# hall-lamp.net
KiCad netlist of a schematic drawn in EAGLE
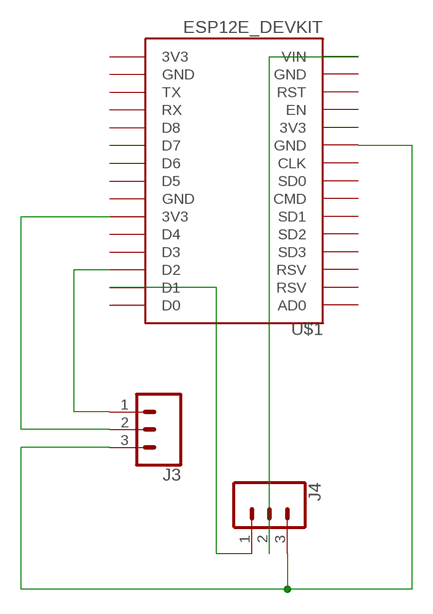
[diagram p0: schematic, sheet 1]

(export (version "E")
  (design (tool "Eeschema 10.0.6"))
  (components
    (comp (ref "J3")
      (value "CONN_03")
      (footprint "eagle-import:1X03")
      (libsource (lib "eagle-import") (part "CONN_03"))
    )
    (comp (ref "J4")
      (value "CONN_03")
      (footprint "eagle-import:1X03")
      (libsource (lib "eagle-import") (part "CONN_03"))
    )
    (comp (ref "U$1")
      (value "ESP12E_DEVKIT")
      (footprint "eagle-import:ESP12E_DEVKIT")
      (libsource (lib "eagle-import") (part "ESP12E_DEVKIT"))
    )
  )
  (nets
    (net (code "1") (name "Net-(J3-Pad1)") (class "Default")
      (node (ref "J3") (pin "1") (pinfunction "1_1") (pintype "passive"))
      (node (ref "U$1") (pin "D2") (pinfunction "D2_D2") (pintype "bidirectional"))
    )
    (net (code "2") (name "Net-(J3-Pad2)") (class "Default")
      (node (ref "J3") (pin "2") (pinfunction "2_2") (pintype "passive"))
      (node (ref "U$1") (pin "3V3@1") (pinfunction "3V3_3V3@1") (pintype "bidirectional"))
    )
    (net (code "3") (name "Net-(J3-Pad3)") (class "Default")
      (node (ref "J3") (pin "3") (pinfunction "3_3") (pintype "passive"))
      (node (ref "J4") (pin "3") (pinfunction "3_3") (pintype "passive"))
      (node (ref "U$1") (pin "GND@0") (pinfunction "GND_GND@0") (pintype "bidirectional"))
    )
    (net (code "4") (name "Net-(J4-Pad1)") (class "Default")
      (node (ref "J4") (pin "1") (pinfunction "1_1") (pintype "passive"))
      (node (ref "U$1") (pin "D1") (pinfunction "D1_D1") (pintype "bidirectional"))
    )
    (net (code "5") (name "Net-(J4-Pad2)") (class "Default")
      (node (ref "J4") (pin "2") (pinfunction "2_2") (pintype "passive"))
      (node (ref "U$1") (pin "VIN") (pinfunction "VIN_VIN") (pintype "bidirectional"))
    )
    (net (code "6") (name "unconnected-(U$1-3V3-Pad3V3@0)") (class "Default")
      (node (ref "U$1") (pin "3V3@0") (pinfunction "3V3_3V3@0") (pintype "bidirectional"))
    )
    (net (code "7") (name "unconnected-(U$1-3V3-Pad3V3@2)") (class "Default")
      (node (ref "U$1") (pin "3V3@2") (pinfunction "3V3_3V3@2") (pintype "bidirectional"))
    )
    (net (code "8") (name "unconnected-(U$1-GND-PadGND@1)") (class "Default")
      (node (ref "U$1") (pin "GND@1") (pinfunction "GND_GND@1") (pintype "bidirectional"))
    )
    (net (code "9") (name "unconnected-(U$1-GND-PadGND@2)") (class "Default")
      (node (ref "U$1") (pin "GND@2") (pinfunction "GND_GND@2") (pintype "bidirectional"))
    )
    (net (code "10") (name "unconnected-(U$1-GND-PadGND@3)") (class "Default")
      (node (ref "U$1") (pin "GND@3") (pinfunction "GND_GND@3") (pintype "bidirectional"))
    )
    (net (code "11") (name "unconnected-(U$1-PadAD0)") (class "Default")
      (node (ref "U$1") (pin "AD0") (pinfunction "AD0_AD0") (pintype "bidirectional"))
    )
    (net (code "12") (name "unconnected-(U$1-PadCLK)") (class "Default")
      (node (ref "U$1") (pin "CLK") (pinfunction "CLK_CLK") (pintype "bidirectional"))
    )
    (net (code "13") (name "unconnected-(U$1-PadCMD)") (class "Default")
      (node (ref "U$1") (pin "CMD") (pinfunction "CMD_CMD") (pintype "bidirectional"))
    )
    (net (code "14") (name "unconnected-(U$1-PadD0)") (class "Default")
      (node (ref "U$1") (pin "D0") (pinfunction "D0_D0") (pintype "bidirectional"))
    )
    (net (code "15") (name "unconnected-(U$1-PadD3)") (class "Default")
      (node (ref "U$1") (pin "D3") (pinfunction "D3_D3") (pintype "bidirectional"))
    )
    (net (code "16") (name "unconnected-(U$1-PadD4)") (class "Default")
      (node (ref "U$1") (pin "D4") (pinfunction "D4_D4") (pintype "bidirectional"))
    )
    (net (code "17") (name "unconnected-(U$1-PadD5)") (class "Default")
      (node (ref "U$1") (pin "D5") (pinfunction "D5_D5") (pintype "bidirectional"))
    )
    (net (code "18") (name "unconnected-(U$1-PadD6)") (class "Default")
      (node (ref "U$1") (pin "D6") (pinfunction "D6_D6") (pintype "bidirectional"))
    )
    (net (code "19") (name "unconnected-(U$1-PadD7)") (class "Default")
      (node (ref "U$1") (pin "D7") (pinfunction "D7_D7") (pintype "bidirectional"))
    )
    (net (code "20") (name "unconnected-(U$1-PadD8)") (class "Default")
      (node (ref "U$1") (pin "D8") (pinfunction "D8_D8") (pintype "bidirectional"))
    )
    (net (code "21") (name "unconnected-(U$1-PadEN)") (class "Default")
      (node (ref "U$1") (pin "EN") (pinfunction "EN_EN") (pintype "bidirectional"))
    )
    (net (code "22") (name "unconnected-(U$1-PadRST)") (class "Default")
      (node (ref "U$1") (pin "RST") (pinfunction "RST_RST") (pintype "bidirectional"))
    )
    (net (code "23") (name "unconnected-(U$1-PadRX)") (class "Default")
      (node (ref "U$1") (pin "RX") (pinfunction "RX_RX") (pintype "bidirectional"))
    )
    (net (code "24") (name "unconnected-(U$1-PadSD0)") (class "Default")
      (node (ref "U$1") (pin "SD0") (pinfunction "SD0_SD0") (pintype "bidirectional"))
    )
    (net (code "25") (name "unconnected-(U$1-PadSD1)") (class "Default")
      (node (ref "U$1") (pin "SD1") (pinfunction "SD1_SD1") (pintype "bidirectional"))
    )
    (net (code "26") (name "unconnected-(U$1-PadSD2)") (class "Default")
      (node (ref "U$1") (pin "SD2") (pinfunction "SD2_SD2") (pintype "bidirectional"))
    )
    (net (code "27") (name "unconnected-(U$1-PadSD3)") (class "Default")
      (node (ref "U$1") (pin "SD3") (pinfunction "SD3_SD3") (pintype "bidirectional"))
    )
    (net (code "28") (name "unconnected-(U$1-PadTX)") (class "Default")
      (node (ref "U$1") (pin "TX") (pinfunction "TX_TX") (pintype "bidirectional"))
    )
    (net (code "29") (name "unconnected-(U$1-RSV-PadRSV@0)") (class "Default")
      (node (ref "U$1") (pin "RSV@0") (pinfunction "RSV_RSV@0") (pintype "bidirectional"))
    )
    (net (code "30") (name "unconnected-(U$1-RSV-PadRSV@1)") (class "Default")
      (node (ref "U$1") (pin "RSV@1") (pinfunction "RSV_RSV@1") (pintype "bidirectional"))
    )
  )
)
